# SCH.net
KiCad netlist of a schematic drawn in EasyEDA
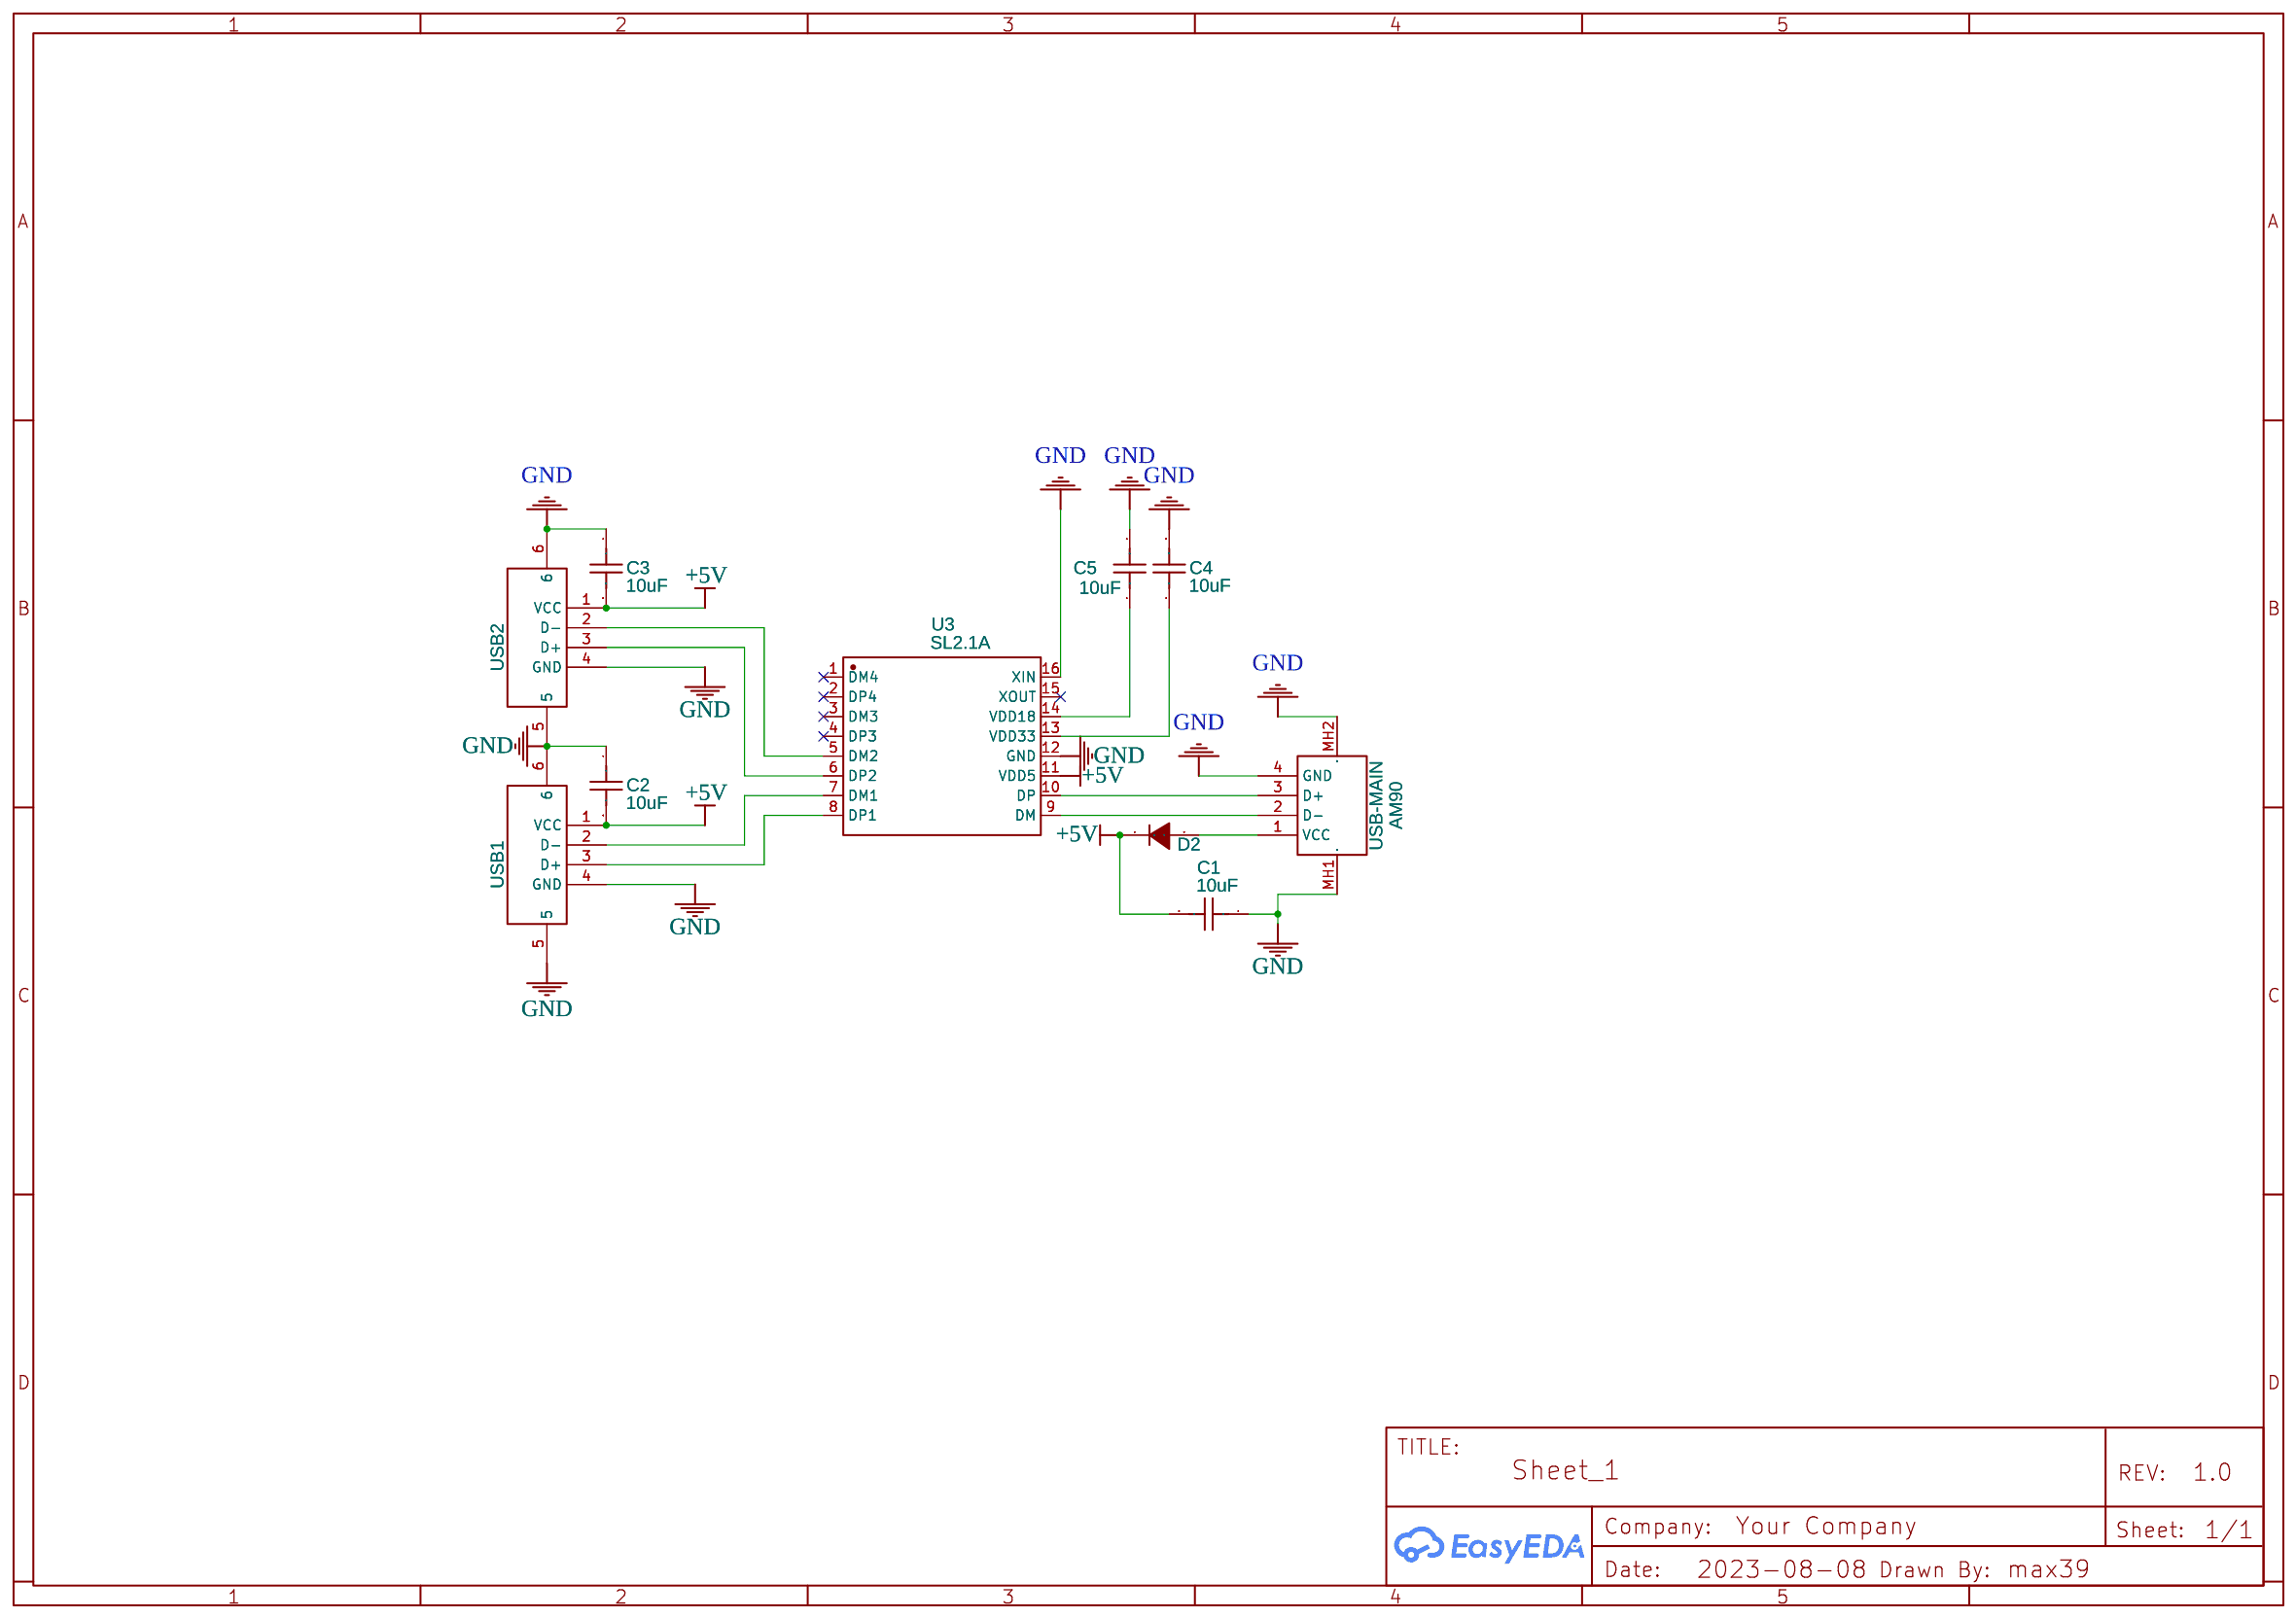
[diagram p0: schematic sheet]

(export (version "E")
  (design (tool "Eeschema 10.0.6"))
  (components
    (comp (ref "C1")
      (value "10uF")
      (fields
        (field (name "Manufacturer Part") "CL10A106KP8NNNC")
        (field (name "Manufacturer") "SAMSUNG(三星)")
      )
      (libsource (lib "") (part "CL10A106KP8NNNC_1"))
    )
    (comp (ref "C2")
      (value "10uF")
      (fields
        (field (name "Manufacturer Part") "CL10A106KP8NNNC")
        (field (name "Manufacturer") "SAMSUNG(三星)")
      )
      (libsource (lib "") (part "CL10A106KP8NNNC"))
    )
    (comp (ref "C3")
      (value "10uF")
      (fields
        (field (name "Manufacturer Part") "CL10A106KP8NNNC")
        (field (name "Manufacturer") "SAMSUNG(三星)")
      )
      (libsource (lib "") (part "CL10A106KP8NNNC"))
    )
    (comp (ref "C4") (value "10uF") (libsource (lib "") (part "C_0603_US")))
    (comp (ref "C5") (value "10uF") (libsource (lib "") (part "C_0603_US")))
    (comp (ref "D2")
      (value "NSR0320MW2T1G")
      (fields (field (name "Manufacturer") "onsemi(安森美)"))
      (libsource (lib "") (part "NSR0320MW2T1G"))
    )
    (comp (ref "U3")
      (value "SL2.1A")
      (fields (field (name "Manufacturer") "CoreChips(和芯润德)"))
      (libsource (lib "") (part "SL2.1A"))
    )
    (comp (ref "USB-MAIN")
      (value "AM90")
      (fields (field (name "Manufacturer") "SHOU HAN(首韩)"))
      (libsource (lib "") (part "AM90"))
    )
    (comp (ref "USB1")
      (value "USB-AF-90-14.4X13.6-H7.0-DIP")
      (fields (field (name "Manufacturer Part") "903-131A1011D10100") (field (name "Manufacturer") "精拓金"))
      (libsource (lib "") (part "USB-AF-90-14.4X13.6-H7.0-DIP"))
    )
    (comp (ref "USB2")
      (value "USB-AF-90-14.4X13.6-H7.0-DIP")
      (fields (field (name "Manufacturer Part") "903-131A1011D10100") (field (name "Manufacturer") "精拓金"))
      (libsource (lib "") (part "USB-AF-90-14.4X13.6-H7.0-DIP"))
    )
  )
  (nets
    (net (code "1") (name "+5V") (class "Default")
      (node (ref "C1") (pin "2") (pinfunction "2_2") (pintype "unspecified"))
      (node (ref "C2") (pin "2") (pinfunction "2_2") (pintype "unspecified"))
      (node (ref "C3") (pin "2") (pinfunction "2_2") (pintype "unspecified"))
      (node (ref "D2") (pin "1") (pinfunction "C_1") (pintype "unspecified"))
      (node (ref "U3") (pin "11") (pinfunction "VDD5_11") (pintype "unspecified"))
      (node (ref "USB1") (pin "1") (pinfunction "VCC_1") (pintype "unspecified"))
      (node (ref "USB2") (pin "1") (pinfunction "VCC_1") (pintype "unspecified"))
    )
    (net (code "2") (name "GND") (class "Default")
      (node (ref "C1") (pin "1") (pinfunction "1_1") (pintype "unspecified"))
      (node (ref "C2") (pin "1") (pinfunction "1_1") (pintype "unspecified"))
      (node (ref "C3") (pin "1") (pinfunction "1_1") (pintype "unspecified"))
      (node (ref "C4") (pin "2") (pinfunction "2_2") (pintype "unspecified"))
      (node (ref "C5") (pin "2") (pinfunction "2_2") (pintype "unspecified"))
      (node (ref "U3") (pin "12") (pinfunction "GND_12") (pintype "unspecified"))
      (node (ref "U3") (pin "16") (pinfunction "XIN_16") (pintype "unspecified"))
      (node (ref "USB-MAIN") (pin "4") (pinfunction "GND_4") (pintype "input"))
      (node (ref "USB-MAIN") (pin "MH1") (pinfunction "MH1_MH1") (pintype "unspecified"))
      (node (ref "USB-MAIN") (pin "MH2") (pinfunction "MH2_MH2") (pintype "unspecified"))
      (node (ref "USB1") (pin "4") (pinfunction "GND_4") (pintype "unspecified"))
      (node (ref "USB1") (pin "5") (pinfunction "5_5") (pintype "unspecified"))
      (node (ref "USB1") (pin "6") (pinfunction "6_6") (pintype "unspecified"))
      (node (ref "USB2") (pin "4") (pinfunction "GND_4") (pintype "unspecified"))
      (node (ref "USB2") (pin "5") (pinfunction "5_5") (pintype "unspecified"))
      (node (ref "USB2") (pin "6") (pinfunction "6_6") (pintype "unspecified"))
    )
    (net (code "3") (name "Net-(D2-A)") (class "Default")
      (node (ref "D2") (pin "2") (pinfunction "A_2") (pintype "unspecified"))
      (node (ref "USB-MAIN") (pin "1") (pinfunction "VCC_1") (pintype "input"))
    )
    (net (code "4") (name "Net-(U3-DM)") (class "Default")
      (node (ref "U3") (pin "9") (pinfunction "DM_9") (pintype "unspecified"))
      (node (ref "USB-MAIN") (pin "2") (pinfunction "D-_2") (pintype "input"))
    )
    (net (code "5") (name "Net-(U3-DM1)") (class "Default")
      (node (ref "U3") (pin "7") (pinfunction "DM1_7") (pintype "unspecified"))
      (node (ref "USB1") (pin "2") (pinfunction "D-_2") (pintype "unspecified"))
    )
    (net (code "6") (name "Net-(U3-DM2)") (class "Default")
      (node (ref "U3") (pin "5") (pinfunction "DM2_5") (pintype "unspecified"))
      (node (ref "USB2") (pin "2") (pinfunction "D-_2") (pintype "unspecified"))
    )
    (net (code "7") (name "Net-(U3-DP)") (class "Default")
      (node (ref "U3") (pin "10") (pinfunction "DP_10") (pintype "unspecified"))
      (node (ref "USB-MAIN") (pin "3") (pinfunction "D+_3") (pintype "input"))
    )
    (net (code "8") (name "Net-(U3-DP1)") (class "Default")
      (node (ref "U3") (pin "8") (pinfunction "DP1_8") (pintype "unspecified"))
      (node (ref "USB1") (pin "3") (pinfunction "D+_3") (pintype "unspecified"))
    )
    (net (code "9") (name "Net-(U3-DP2)") (class "Default")
      (node (ref "U3") (pin "6") (pinfunction "DP2_6") (pintype "unspecified"))
      (node (ref "USB2") (pin "3") (pinfunction "D+_3") (pintype "unspecified"))
    )
    (net (code "10") (name "Net-(U3-VDD18)") (class "Default")
      (node (ref "C5") (pin "1") (pinfunction "1_1") (pintype "unspecified"))
      (node (ref "U3") (pin "14") (pinfunction "VDD18_14") (pintype "unspecified"))
    )
    (net (code "11") (name "Net-(U3-VDD33)") (class "Default")
      (node (ref "C4") (pin "1") (pinfunction "1_1") (pintype "unspecified"))
      (node (ref "U3") (pin "13") (pinfunction "VDD33_13") (pintype "unspecified"))
    )
    (net (code "12") (name "unconnected-(U3-DM3-Pad3)") (class "Default")
      (node (ref "U3") (pin "3") (pinfunction "DM3_3") (pintype "unspecified+no_connect"))
    )
    (net (code "13") (name "unconnected-(U3-DM4-Pad1)") (class "Default")
      (node (ref "U3") (pin "1") (pinfunction "DM4_1") (pintype "unspecified+no_connect"))
    )
    (net (code "14") (name "unconnected-(U3-DP3-Pad4)") (class "Default")
      (node (ref "U3") (pin "4") (pinfunction "DP3_4") (pintype "unspecified+no_connect"))
    )
    (net (code "15") (name "unconnected-(U3-DP4-Pad2)") (class "Default")
      (node (ref "U3") (pin "2") (pinfunction "DP4_2") (pintype "unspecified+no_connect"))
    )
    (net (code "16") (name "unconnected-(U3-XOUT-Pad15)") (class "Default")
      (node (ref "U3") (pin "15") (pinfunction "XOUT_15") (pintype "unspecified+no_connect"))
    )
  )
)
